# mma7260_tinybreakout.net
KiCad netlist of a schematic drawn in EAGLE
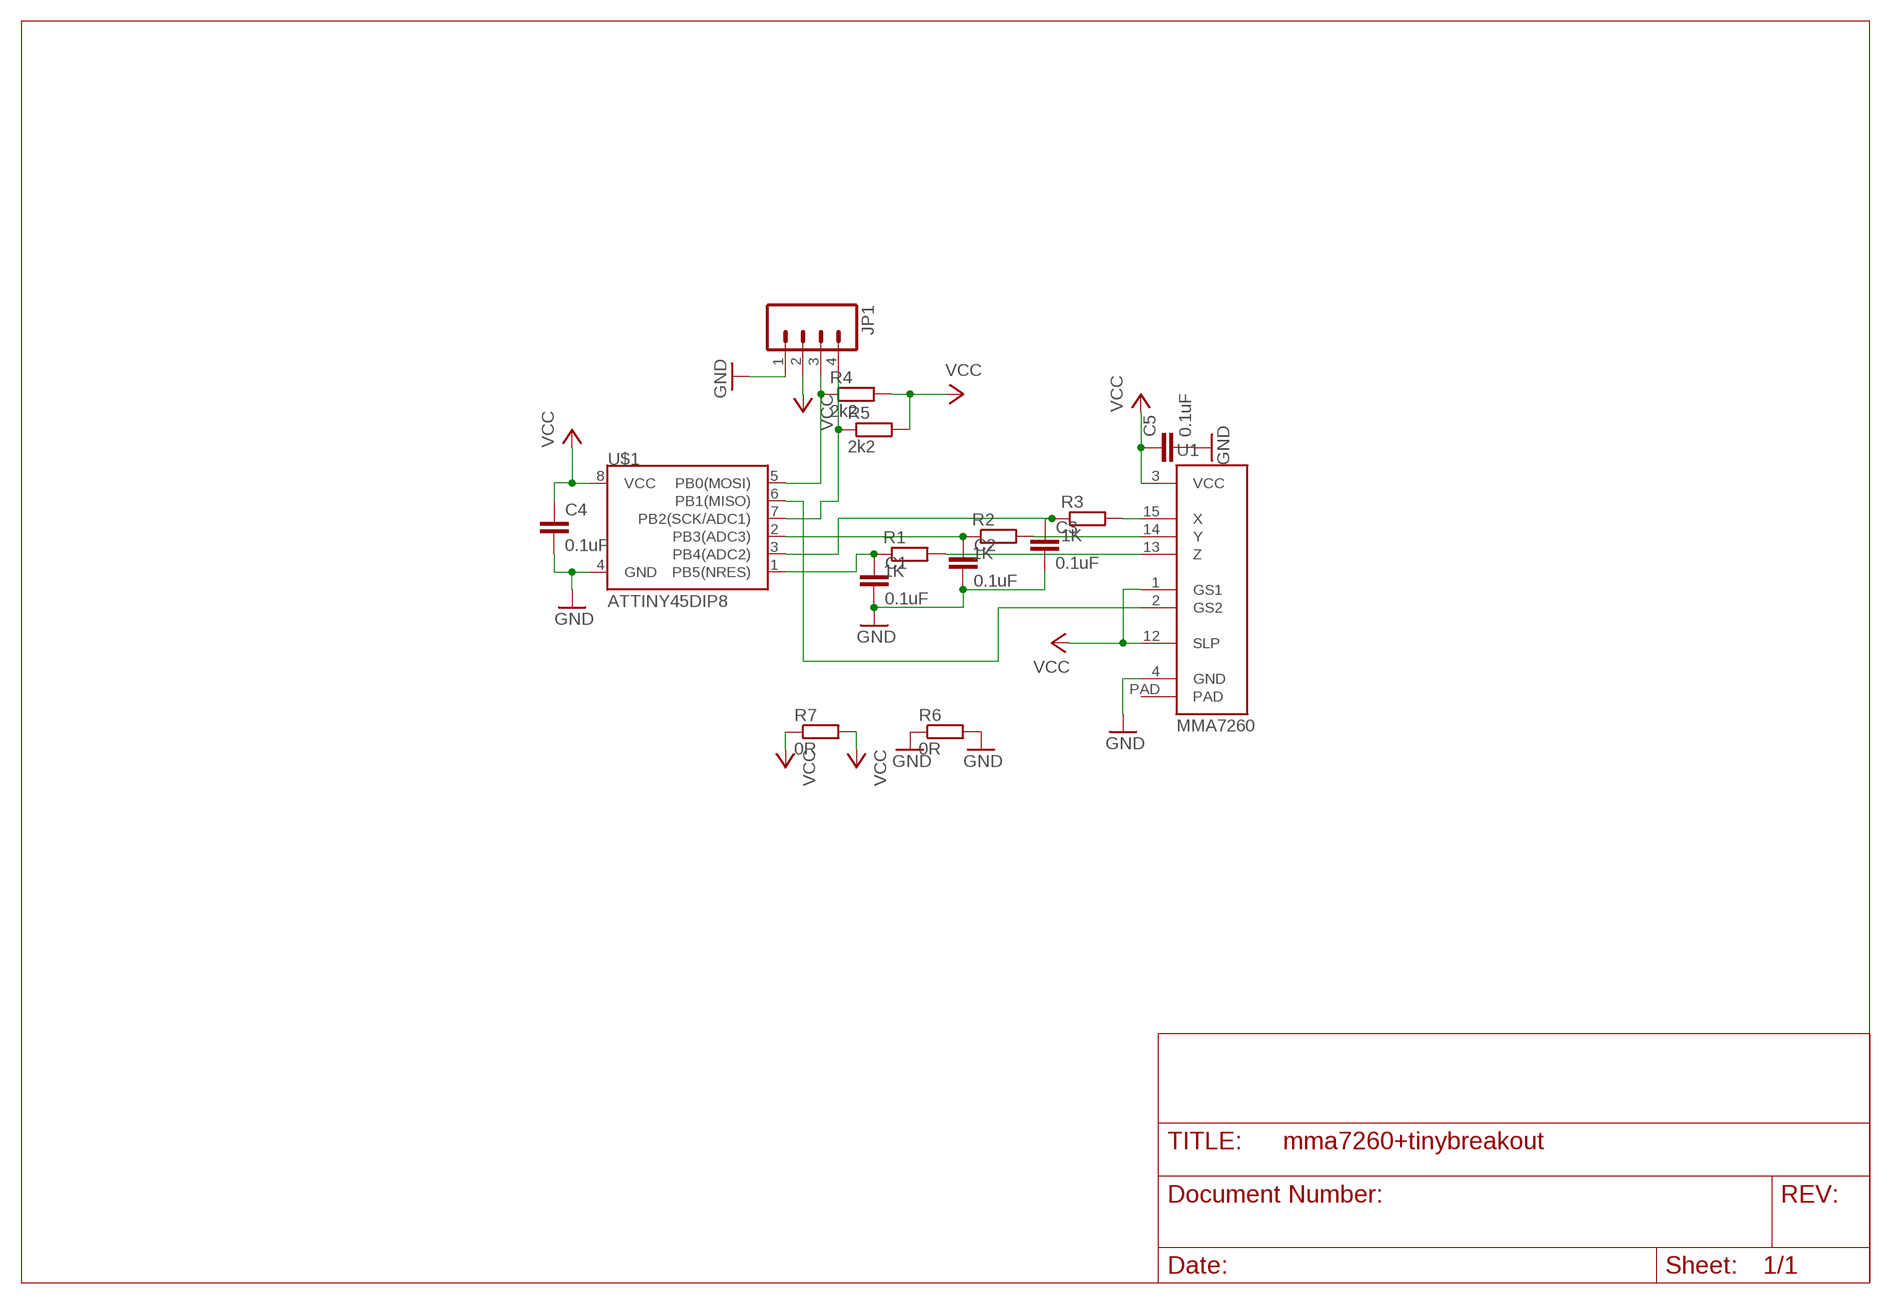
[diagram p0: schematic, sheet 1]

(export (version "E")
  (design (tool "Eeschema 10.0.6"))
  (components
    (comp (ref "C1")
      (value "0.1uF")
      (footprint "eagle-import:C1206")
      (libsource (lib "eagle-import") (part "C-EUC1206"))
    )
    (comp (ref "C2")
      (value "0.1uF")
      (footprint "eagle-import:C1206")
      (libsource (lib "eagle-import") (part "C-EUC1206"))
    )
    (comp (ref "C3")
      (value "0.1uF")
      (footprint "eagle-import:C1206")
      (libsource (lib "eagle-import") (part "C-EUC1206"))
    )
    (comp (ref "C4")
      (value "0.1uF")
      (footprint "eagle-import:C1206")
      (libsource (lib "eagle-import") (part "C-EUC1206"))
    )
    (comp (ref "C5")
      (value "0.1uF")
      (footprint "eagle-import:C1206")
      (libsource (lib "eagle-import") (part "C-EUC1206"))
    )
    (comp (ref "JP1")
      (value "M04LOCK")
      (footprint "eagle-import:1X04_LOCK")
      (libsource (lib "eagle-import") (part "M04LOCK"))
    )
    (comp (ref "R1")
      (value "1K")
      (footprint "eagle-import:R0805")
      (libsource (lib "eagle-import") (part "R-EU_R0805"))
    )
    (comp (ref "R2")
      (value "1K")
      (footprint "eagle-import:R0805")
      (libsource (lib "eagle-import") (part "R-EU_R0805"))
    )
    (comp (ref "R3")
      (value "1K")
      (footprint "eagle-import:R0805")
      (libsource (lib "eagle-import") (part "R-EU_R0805"))
    )
    (comp (ref "R4")
      (value "2k2")
      (footprint "eagle-import:R0805")
      (libsource (lib "eagle-import") (part "R-EU_R0805"))
    )
    (comp (ref "R5")
      (value "2k2")
      (footprint "eagle-import:R0805")
      (libsource (lib "eagle-import") (part "R-EU_R0805"))
    )
    (comp (ref "R6")
      (value "0R")
      (footprint "eagle-import:R1206")
      (libsource (lib "eagle-import") (part "R-EU_R1206"))
    )
    (comp (ref "R7")
      (value "0R")
      (footprint "eagle-import:R1206")
      (libsource (lib "eagle-import") (part "R-EU_R1206"))
    )
    (comp (ref "U$1")
      (value "ATTINY45DIP8")
      (footprint "eagle-import:DIP08")
      (libsource (lib "eagle-import") (part "ATTINY45DIP8"))
    )
    (comp (ref "U1")
      (value "MMA7260")
      (footprint "eagle-import:MMA7260")
      (libsource (lib "eagle-import") (part "MMA7260"))
    )
  )
  (nets
    (net (code "1") (name "GND") (class "Default")
      (node (ref "C1") (pin "2") (pinfunction "2_2") (pintype "passive"))
      (node (ref "C2") (pin "2") (pinfunction "2_2") (pintype "passive"))
      (node (ref "C3") (pin "2") (pinfunction "2_2") (pintype "passive"))
      (node (ref "C4") (pin "2") (pinfunction "2_2") (pintype "passive"))
      (node (ref "C5") (pin "2") (pinfunction "2_2") (pintype "passive"))
      (node (ref "JP1") (pin "1") (pinfunction "1_1") (pintype "passive"))
      (node (ref "R6") (pin "1") (pinfunction "1_1") (pintype "passive"))
      (node (ref "R6") (pin "2") (pinfunction "2_2") (pintype "passive"))
      (node (ref "U$1") (pin "4") (pinfunction "GND_4") (pintype "bidirectional"))
      (node (ref "U1") (pin "4") (pinfunction "GND_4") (pintype "bidirectional"))
    )
    (net (code "2") (name "Net-(U$1-PB0(MOSI))") (class "Default")
      (node (ref "JP1") (pin "3") (pinfunction "3_3") (pintype "passive"))
      (node (ref "R4") (pin "1") (pinfunction "1_1") (pintype "passive"))
      (node (ref "U$1") (pin "5") (pinfunction "PB0(MOSI)_5") (pintype "bidirectional"))
    )
    (net (code "3") (name "Net-(U$1-PB1(MISO))") (class "Default")
      (node (ref "U$1") (pin "6") (pinfunction "PB1(MISO)_6") (pintype "bidirectional"))
      (node (ref "U1") (pin "2") (pinfunction "GS2_2") (pintype "bidirectional"))
    )
    (net (code "4") (name "Net-(U$1-PB2(SCK{slash}ADC1))") (class "Default")
      (node (ref "JP1") (pin "4") (pinfunction "4_4") (pintype "passive"))
      (node (ref "R5") (pin "1") (pinfunction "1_1") (pintype "passive"))
      (node (ref "U$1") (pin "7") (pinfunction "PB2(SCK/ADC1)_7") (pintype "bidirectional"))
    )
    (net (code "5") (name "Net-(U$1-PB3(ADC3))") (class "Default")
      (node (ref "C2") (pin "1") (pinfunction "1_1") (pintype "passive"))
      (node (ref "R2") (pin "1") (pinfunction "1_1") (pintype "passive"))
      (node (ref "U$1") (pin "2") (pinfunction "PB3(ADC3)_2") (pintype "bidirectional"))
    )
    (net (code "6") (name "Net-(U$1-PB4(ADC2))") (class "Default")
      (node (ref "C3") (pin "1") (pinfunction "1_1") (pintype "passive"))
      (node (ref "R3") (pin "1") (pinfunction "1_1") (pintype "passive"))
      (node (ref "U$1") (pin "3") (pinfunction "PB4(ADC2)_3") (pintype "bidirectional"))
    )
    (net (code "7") (name "Net-(U$1-PB5(NRES))") (class "Default")
      (node (ref "C1") (pin "1") (pinfunction "1_1") (pintype "passive"))
      (node (ref "R1") (pin "1") (pinfunction "1_1") (pintype "passive"))
      (node (ref "U$1") (pin "1") (pinfunction "PB5(NRES)_1") (pintype "bidirectional"))
    )
    (net (code "8") (name "Net-(U1-X)") (class "Default")
      (node (ref "R3") (pin "2") (pinfunction "2_2") (pintype "passive"))
      (node (ref "U1") (pin "15") (pinfunction "X_15") (pintype "bidirectional"))
    )
    (net (code "9") (name "Net-(U1-Y)") (class "Default")
      (node (ref "R2") (pin "2") (pinfunction "2_2") (pintype "passive"))
      (node (ref "U1") (pin "14") (pinfunction "Y_14") (pintype "bidirectional"))
    )
    (net (code "10") (name "Net-(U1-Z)") (class "Default")
      (node (ref "R1") (pin "2") (pinfunction "2_2") (pintype "passive"))
      (node (ref "U1") (pin "13") (pinfunction "Z_13") (pintype "bidirectional"))
    )
    (net (code "11") (name "VCC") (class "Default")
      (node (ref "C4") (pin "1") (pinfunction "1_1") (pintype "passive"))
      (node (ref "C5") (pin "1") (pinfunction "1_1") (pintype "passive"))
      (node (ref "JP1") (pin "2") (pinfunction "2_2") (pintype "passive"))
      (node (ref "R4") (pin "2") (pinfunction "2_2") (pintype "passive"))
      (node (ref "R5") (pin "2") (pinfunction "2_2") (pintype "passive"))
      (node (ref "R7") (pin "1") (pinfunction "1_1") (pintype "passive"))
      (node (ref "R7") (pin "2") (pinfunction "2_2") (pintype "passive"))
      (node (ref "U$1") (pin "8") (pinfunction "VCC_8") (pintype "bidirectional"))
      (node (ref "U1") (pin "1") (pinfunction "GS1_1") (pintype "bidirectional"))
      (node (ref "U1") (pin "12") (pinfunction "SLP_12") (pintype "bidirectional"))
      (node (ref "U1") (pin "3") (pinfunction "VCC_3") (pintype "bidirectional"))
    )
    (net (code "12") (name "unconnected-(U1-PadPAD)") (class "Default")
      (node (ref "U1") (pin "PAD") (pinfunction "PAD_PAD") (pintype "bidirectional"))
    )
  )
)
